# openLRS-APM.net
KiCad netlist of a schematic drawn in EAGLE
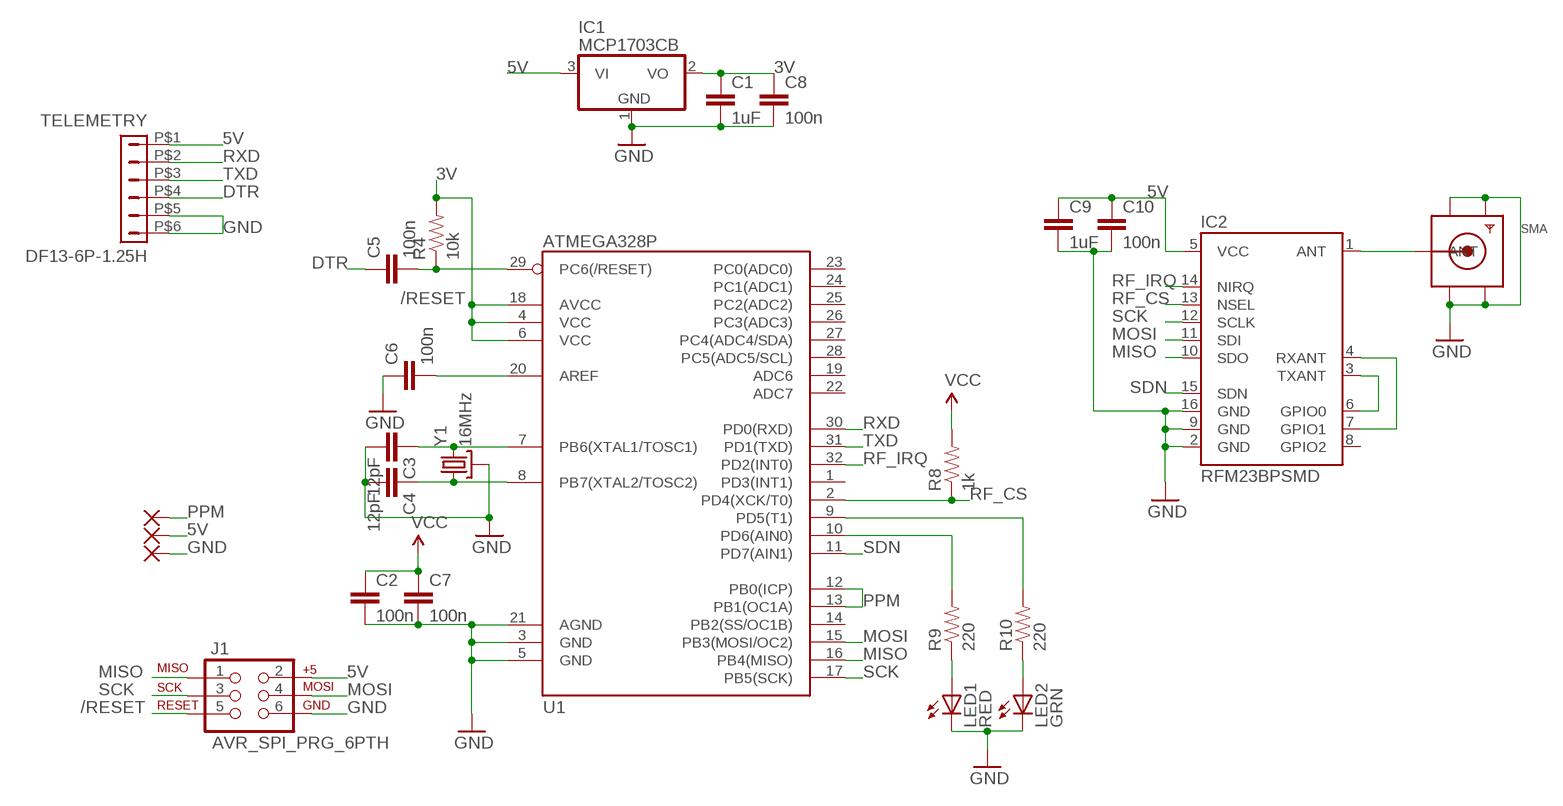
[diagram p0: schematic, sheet 1]

(export (version "E")
  (design (tool "Eeschema 10.0.6"))
  (components
    (comp (ref "C1")
      (value "1uF")
      (footprint "eagle-import:0805")
      (libsource (lib "eagle-import") (part "CAP0805"))
    )
    (comp (ref "C2")
      (value "100n")
      (footprint "eagle-import:0805")
      (libsource (lib "eagle-import") (part "CAP0805"))
    )
    (comp (ref "C3")
      (value "12pF")
      (footprint "eagle-import:0805")
      (libsource (lib "eagle-import") (part "CAP0805"))
    )
    (comp (ref "C4")
      (value "12pF")
      (footprint "eagle-import:0805")
      (libsource (lib "eagle-import") (part "CAP0805"))
    )
    (comp (ref "C5")
      (value "100n")
      (footprint "eagle-import:0805")
      (libsource (lib "eagle-import") (part "CAP0805"))
    )
    (comp (ref "C6")
      (value "100n")
      (footprint "eagle-import:0805")
      (libsource (lib "eagle-import") (part "CAP0805"))
    )
    (comp (ref "C7")
      (value "100n")
      (footprint "eagle-import:0805")
      (libsource (lib "eagle-import") (part "CAP0805"))
    )
    (comp (ref "C8")
      (value "100n")
      (footprint "eagle-import:0805")
      (libsource (lib "eagle-import") (part "CAP0805"))
    )
    (comp (ref "C9")
      (value "1uF")
      (footprint "eagle-import:0805")
      (libsource (lib "eagle-import") (part "CAP0805"))
    )
    (comp (ref "C10")
      (value "100n")
      (footprint "eagle-import:0805")
      (libsource (lib "eagle-import") (part "CAP0805"))
    )
    (comp (ref "GND")
      (value "WIREPADSMD1,27-254")
      (footprint "eagle-import:SMD1,27-2,54")
      (libsource (lib "eagle-import") (part "WIREPADSMD1,27-254"))
    )
    (comp (ref "IC1")
      (value "MCP1703CB")
      (footprint "eagle-import:SOT23")
      (libsource (lib "eagle-import") (part "MCP1703CB"))
    )
    (comp (ref "IC2")
      (value "RFM23BPSMD")
      (footprint "eagle-import:RFM23BP-S2")
      (libsource (lib "eagle-import") (part "RFM23BPSMD"))
    )
    (comp (ref "J1")
      (value "AVR_SPI_PRG_6PTH")
      (footprint "eagle-import:2X3")
      (libsource (lib "eagle-import") (part "AVR_SPI_PRG_6PTH"))
    )
    (comp (ref "LED1")
      (value "RED")
      (footprint "eagle-import:SML0805")
      (libsource (lib "eagle-import") (part "LEDSML0805"))
    )
    (comp (ref "LED2")
      (value "GRN")
      (footprint "eagle-import:SML0805")
      (libsource (lib "eagle-import") (part "LEDSML0805"))
    )
    (comp (ref "PPM")
      (value "WIREPADSMD1,27-254")
      (footprint "eagle-import:SMD1,27-2,54")
      (libsource (lib "eagle-import") (part "WIREPADSMD1,27-254"))
    )
    (comp (ref "R4")
      (value "10k")
      (footprint "eagle-import:0805")
      (libsource (lib "eagle-import") (part "RESISTOR0805-RES"))
    )
    (comp (ref "R8")
      (value "1k")
      (footprint "eagle-import:0805")
      (libsource (lib "eagle-import") (part "RESISTOR0805-RES"))
    )
    (comp (ref "R9")
      (value "220")
      (footprint "eagle-import:0805")
      (libsource (lib "eagle-import") (part "RESISTOR0805-RES"))
    )
    (comp (ref "R10")
      (value "220")
      (footprint "eagle-import:0805")
      (libsource (lib "eagle-import") (part "RESISTOR0805-RES"))
    )
    (comp (ref "SMA")
      (value "SMACONNECTOR_EDGE")
      (footprint "eagle-import:SMA_EDGELAUNCH")
      (libsource (lib "eagle-import") (part "SMACONNECTOR_EDGE"))
    )
    (comp (ref "TELEMETRY")
      (value "DF13-6P-1.25H")
      (footprint "eagle-import:DF13A-6P-1.25H")
      (libsource (lib "eagle-import") (part "DF13-6P-1.25H"))
    )
    (comp (ref "U1")
      (value "ATMEGA328P")
      (footprint "eagle-import:TQFP32-08")
      (libsource (lib "eagle-import") (part "ATMEGA328_SMT"))
    )
    (comp (ref "VCC")
      (value "WIREPADSMD1,27-254")
      (footprint "eagle-import:SMD1,27-2,54")
      (libsource (lib "eagle-import") (part "WIREPADSMD1,27-254"))
    )
    (comp (ref "Y1")
      (value "16MHz")
      (footprint "eagle-import:CRYSTAL-SMD-5X3")
      (libsource (lib "eagle-import") (part "CRYSTAL3.2X2.5"))
    )
  )
  (nets
    (net (code "1") (name "/3V") (class "Default")
      (node (ref "C1") (pin "1") (pinfunction "1_1") (pintype "passive"))
      (node (ref "C8") (pin "1") (pinfunction "1_1") (pintype "passive"))
      (node (ref "IC1") (pin "2") (pinfunction "VO_2") (pintype "passive"))
      (node (ref "R4") (pin "2") (pinfunction "2_2") (pintype "passive"))
      (node (ref "U1") (pin "18") (pinfunction "AVCC_18") (pintype "bidirectional"))
      (node (ref "U1") (pin "4") (pinfunction "VCC_4") (pintype "bidirectional"))
      (node (ref "U1") (pin "6") (pinfunction "VCC_6") (pintype "bidirectional"))
    )
    (net (code "2") (name "/5V") (class "Default")
      (node (ref "C10") (pin "1") (pinfunction "1_1") (pintype "passive"))
      (node (ref "C9") (pin "1") (pinfunction "1_1") (pintype "passive"))
      (node (ref "IC1") (pin "3") (pinfunction "VI_3") (pintype "input"))
      (node (ref "IC2") (pin "5") (pinfunction "VCC_5") (pintype "bidirectional"))
      (node (ref "J1") (pin "2") (pinfunction "2_2") (pintype "passive"))
      (node (ref "TELEMETRY") (pin "P$1") (pinfunction "1_P$1") (pintype "passive"))
      (node (ref "VCC") (pin "1") (pinfunction "P_1") (pintype "passive"))
    )
    (net (code "3") (name "/DTR") (class "Default")
      (node (ref "C5") (pin "1") (pinfunction "1_1") (pintype "passive"))
      (node (ref "TELEMETRY") (pin "P$4") (pinfunction "4_P$4") (pintype "passive"))
    )
    (net (code "4") (name "/MISO") (class "Default")
      (node (ref "IC2") (pin "10") (pinfunction "SDO_10") (pintype "output"))
      (node (ref "J1") (pin "1") (pinfunction "1_1") (pintype "passive"))
      (node (ref "U1") (pin "16") (pinfunction "PB4(MISO)_16") (pintype "bidirectional"))
    )
    (net (code "5") (name "/MOSI") (class "Default")
      (node (ref "IC2") (pin "11") (pinfunction "SDI_11") (pintype "input"))
      (node (ref "J1") (pin "4") (pinfunction "4_4") (pintype "passive"))
      (node (ref "U1") (pin "15") (pinfunction "PB3(MOSI/OC2)_15") (pintype "bidirectional"))
    )
    (net (code "6") (name "/PPM") (class "Default")
      (node (ref "PPM") (pin "1") (pinfunction "P_1") (pintype "passive"))
      (node (ref "U1") (pin "12") (pinfunction "PB0(ICP)_12") (pintype "bidirectional"))
      (node (ref "U1") (pin "13") (pinfunction "PB1(OC1A)_13") (pintype "bidirectional"))
    )
    (net (code "7") (name "/RF_CS") (class "Default")
      (node (ref "IC2") (pin "13") (pinfunction "NSEL_13") (pintype "input"))
      (node (ref "R8") (pin "1") (pinfunction "1_1") (pintype "passive"))
      (node (ref "U1") (pin "2") (pinfunction "PD4(XCK/T0)_2") (pintype "bidirectional"))
    )
    (net (code "8") (name "/RF_IRQ") (class "Default")
      (node (ref "IC2") (pin "14") (pinfunction "NIRQ_14") (pintype "output"))
      (node (ref "U1") (pin "32") (pinfunction "PD2(INT0)_32") (pintype "bidirectional"))
    )
    (net (code "9") (name "/RXD") (class "Default")
      (node (ref "TELEMETRY") (pin "P$2") (pinfunction "2_P$2") (pintype "passive"))
      (node (ref "U1") (pin "30") (pinfunction "PD0(RXD)_30") (pintype "bidirectional"))
    )
    (net (code "10") (name "/SCK") (class "Default")
      (node (ref "IC2") (pin "12") (pinfunction "SCLK_12") (pintype "input"))
      (node (ref "J1") (pin "3") (pinfunction "3_3") (pintype "passive"))
      (node (ref "U1") (pin "17") (pinfunction "PB5(SCK)_17") (pintype "bidirectional"))
    )
    (net (code "11") (name "/SDN") (class "Default")
      (node (ref "IC2") (pin "15") (pinfunction "SDN_15") (pintype "input"))
      (node (ref "U1") (pin "11") (pinfunction "PD7(AIN1)_11") (pintype "bidirectional"))
    )
    (net (code "12") (name "/TXD") (class "Default")
      (node (ref "TELEMETRY") (pin "P$3") (pinfunction "3_P$3") (pintype "passive"))
      (node (ref "U1") (pin "31") (pinfunction "PD1(TXD)_31") (pintype "bidirectional"))
    )
    (net (code "13") (name "/{slash}RESET") (class "Default")
      (node (ref "C5") (pin "2") (pinfunction "2_2") (pintype "passive"))
      (node (ref "J1") (pin "5") (pinfunction "5_5") (pintype "passive"))
      (node (ref "R4") (pin "1") (pinfunction "1_1") (pintype "passive"))
      (node (ref "U1") (pin "29") (pinfunction "PC6(/RESET)_29") (pintype "bidirectional"))
    )
    (net (code "14") (name "GND") (class "Default")
      (node (ref "C1") (pin "2") (pinfunction "2_2") (pintype "passive"))
      (node (ref "C10") (pin "2") (pinfunction "2_2") (pintype "passive"))
      (node (ref "C2") (pin "2") (pinfunction "2_2") (pintype "passive"))
      (node (ref "C3") (pin "2") (pinfunction "2_2") (pintype "passive"))
      (node (ref "C4") (pin "2") (pinfunction "2_2") (pintype "passive"))
      (node (ref "C6") (pin "1") (pinfunction "1_1") (pintype "passive"))
      (node (ref "C7") (pin "2") (pinfunction "2_2") (pintype "passive"))
      (node (ref "C8") (pin "2") (pinfunction "2_2") (pintype "passive"))
      (node (ref "C9") (pin "2") (pinfunction "2_2") (pintype "passive"))
      (node (ref "GND") (pin "1") (pinfunction "P_1") (pintype "passive"))
      (node (ref "IC1") (pin "1") (pinfunction "GND_1") (pintype "passive"))
      (node (ref "IC2") (pin "16") (pinfunction "GND_16") (pintype "power_in"))
      (node (ref "IC2") (pin "2") (pinfunction "GND_2") (pintype "power_in"))
      (node (ref "IC2") (pin "9") (pinfunction "GND_9") (pintype "power_in"))
      (node (ref "J1") (pin "6") (pinfunction "6_6") (pintype "passive"))
      (node (ref "LED1") (pin "C") (pinfunction "C_C") (pintype "passive"))
      (node (ref "LED2") (pin "C") (pinfunction "C_C") (pintype "passive"))
      (node (ref "SMA") (pin "GND@1") (pinfunction "GND4_GND@1") (pintype "power_in"))
      (node (ref "SMA") (pin "GND@2") (pinfunction "GND3_GND@2") (pintype "power_in"))
      (node (ref "SMA") (pin "GND@3") (pinfunction "GND2_GND@3") (pintype "power_in"))
      (node (ref "SMA") (pin "GND@4") (pinfunction "GND1_GND@4") (pintype "power_in"))
      (node (ref "TELEMETRY") (pin "P$5") (pinfunction "5_P$5") (pintype "passive"))
      (node (ref "TELEMETRY") (pin "P$6") (pinfunction "6_P$6") (pintype "passive"))
      (node (ref "U1") (pin "21") (pinfunction "AGND_21") (pintype "bidirectional"))
      (node (ref "U1") (pin "3") (pinfunction "GND_3") (pintype "bidirectional"))
      (node (ref "U1") (pin "5") (pinfunction "GND_5") (pintype "bidirectional"))
      (node (ref "Y1") (pin "2") (pinfunction "GND_2") (pintype "power_in"))
      (node (ref "Y1") (pin "4") (pinfunction "GND_4") (pintype "power_in"))
    )
    (net (code "15") (name "Net-(IC2-ANT)") (class "Default")
      (node (ref "IC2") (pin "1") (pinfunction "ANT_1") (pintype "bidirectional"))
      (node (ref "SMA") (pin "P") (pinfunction "ANT_P") (pintype "bidirectional"))
    )
    (net (code "16") (name "Net-(IC2-GPIO0)") (class "Default")
      (node (ref "IC2") (pin "3") (pinfunction "TXANT_3") (pintype "input"))
      (node (ref "IC2") (pin "6") (pinfunction "GPIO0_6") (pintype "bidirectional"))
    )
    (net (code "17") (name "Net-(IC2-GPIO1)") (class "Default")
      (node (ref "IC2") (pin "4") (pinfunction "RXANT_4") (pintype "input"))
      (node (ref "IC2") (pin "7") (pinfunction "GPIO1_7") (pintype "bidirectional"))
    )
    (net (code "18") (name "Net-(LED1-PadA)") (class "Default")
      (node (ref "LED1") (pin "A") (pinfunction "A_A") (pintype "passive"))
      (node (ref "R9") (pin "1") (pinfunction "1_1") (pintype "passive"))
    )
    (net (code "19") (name "Net-(LED2-PadA)") (class "Default")
      (node (ref "LED2") (pin "A") (pinfunction "A_A") (pintype "passive"))
      (node (ref "R10") (pin "1") (pinfunction "1_1") (pintype "passive"))
    )
    (net (code "20") (name "Net-(U1-AREF)") (class "Default")
      (node (ref "C6") (pin "2") (pinfunction "2_2") (pintype "passive"))
      (node (ref "U1") (pin "20") (pinfunction "AREF_20") (pintype "bidirectional"))
    )
    (net (code "21") (name "Net-(U1-PB6(XTAL1{slash}TOSC1))") (class "Default")
      (node (ref "C3") (pin "1") (pinfunction "1_1") (pintype "passive"))
      (node (ref "U1") (pin "7") (pinfunction "PB6(XTAL1/TOSC1)_7") (pintype "bidirectional"))
      (node (ref "Y1") (pin "3") (pinfunction "2_3") (pintype "passive"))
    )
    (net (code "22") (name "Net-(U1-PB7(XTAL2{slash}TOSC2))") (class "Default")
      (node (ref "C4") (pin "1") (pinfunction "1_1") (pintype "passive"))
      (node (ref "U1") (pin "8") (pinfunction "PB7(XTAL2/TOSC2)_8") (pintype "bidirectional"))
      (node (ref "Y1") (pin "1") (pinfunction "1_1") (pintype "passive"))
    )
    (net (code "23") (name "Net-(U1-PD5(T1))") (class "Default")
      (node (ref "R10") (pin "2") (pinfunction "2_2") (pintype "passive"))
      (node (ref "U1") (pin "9") (pinfunction "PD5(T1)_9") (pintype "bidirectional"))
    )
    (net (code "24") (name "Net-(U1-PD6(AIN0))") (class "Default")
      (node (ref "R9") (pin "2") (pinfunction "2_2") (pintype "passive"))
      (node (ref "U1") (pin "10") (pinfunction "PD6(AIN0)_10") (pintype "bidirectional"))
    )
    (net (code "25") (name "VCC") (class "Default")
      (node (ref "C2") (pin "1") (pinfunction "1_1") (pintype "passive"))
      (node (ref "C7") (pin "1") (pinfunction "1_1") (pintype "passive"))
      (node (ref "R8") (pin "2") (pinfunction "2_2") (pintype "passive"))
    )
    (net (code "26") (name "unconnected-(IC2-GPIO2-Pad8)") (class "Default")
      (node (ref "IC2") (pin "8") (pinfunction "GPIO2_8") (pintype "bidirectional"))
    )
    (net (code "27") (name "unconnected-(U1-ADC6-Pad19)") (class "Default")
      (node (ref "U1") (pin "19") (pinfunction "ADC6_19") (pintype "bidirectional"))
    )
    (net (code "28") (name "unconnected-(U1-ADC7-Pad22)") (class "Default")
      (node (ref "U1") (pin "22") (pinfunction "ADC7_22") (pintype "bidirectional"))
    )
    (net (code "29") (name "unconnected-(U1-PB2(SS{slash}OC1B)-Pad14)") (class "Default")
      (node (ref "U1") (pin "14") (pinfunction "PB2(SS/OC1B)_14") (pintype "bidirectional"))
    )
    (net (code "30") (name "unconnected-(U1-PC0(ADC0)-Pad23)") (class "Default")
      (node (ref "U1") (pin "23") (pinfunction "PC0(ADC0)_23") (pintype "bidirectional"))
    )
    (net (code "31") (name "unconnected-(U1-PC1(ADC1)-Pad24)") (class "Default")
      (node (ref "U1") (pin "24") (pinfunction "PC1(ADC1)_24") (pintype "bidirectional"))
    )
    (net (code "32") (name "unconnected-(U1-PC2(ADC2)-Pad25)") (class "Default")
      (node (ref "U1") (pin "25") (pinfunction "PC2(ADC2)_25") (pintype "bidirectional"))
    )
    (net (code "33") (name "unconnected-(U1-PC3(ADC3)-Pad26)") (class "Default")
      (node (ref "U1") (pin "26") (pinfunction "PC3(ADC3)_26") (pintype "bidirectional"))
    )
    (net (code "34") (name "unconnected-(U1-PC4(ADC4{slash}SDA)-Pad27)") (class "Default")
      (node (ref "U1") (pin "27") (pinfunction "PC4(ADC4/SDA)_27") (pintype "bidirectional"))
    )
    (net (code "35") (name "unconnected-(U1-PC5(ADC5{slash}SCL)-Pad28)") (class "Default")
      (node (ref "U1") (pin "28") (pinfunction "PC5(ADC5/SCL)_28") (pintype "bidirectional"))
    )
    (net (code "36") (name "unconnected-(U1-PD3(INT1)-Pad1)") (class "Default")
      (node (ref "U1") (pin "1") (pinfunction "PD3(INT1)_1") (pintype "bidirectional"))
    )
  )
)
